# comms_sys_schematic_V1.net
KiCad netlist of a schematic drawn in EAGLE
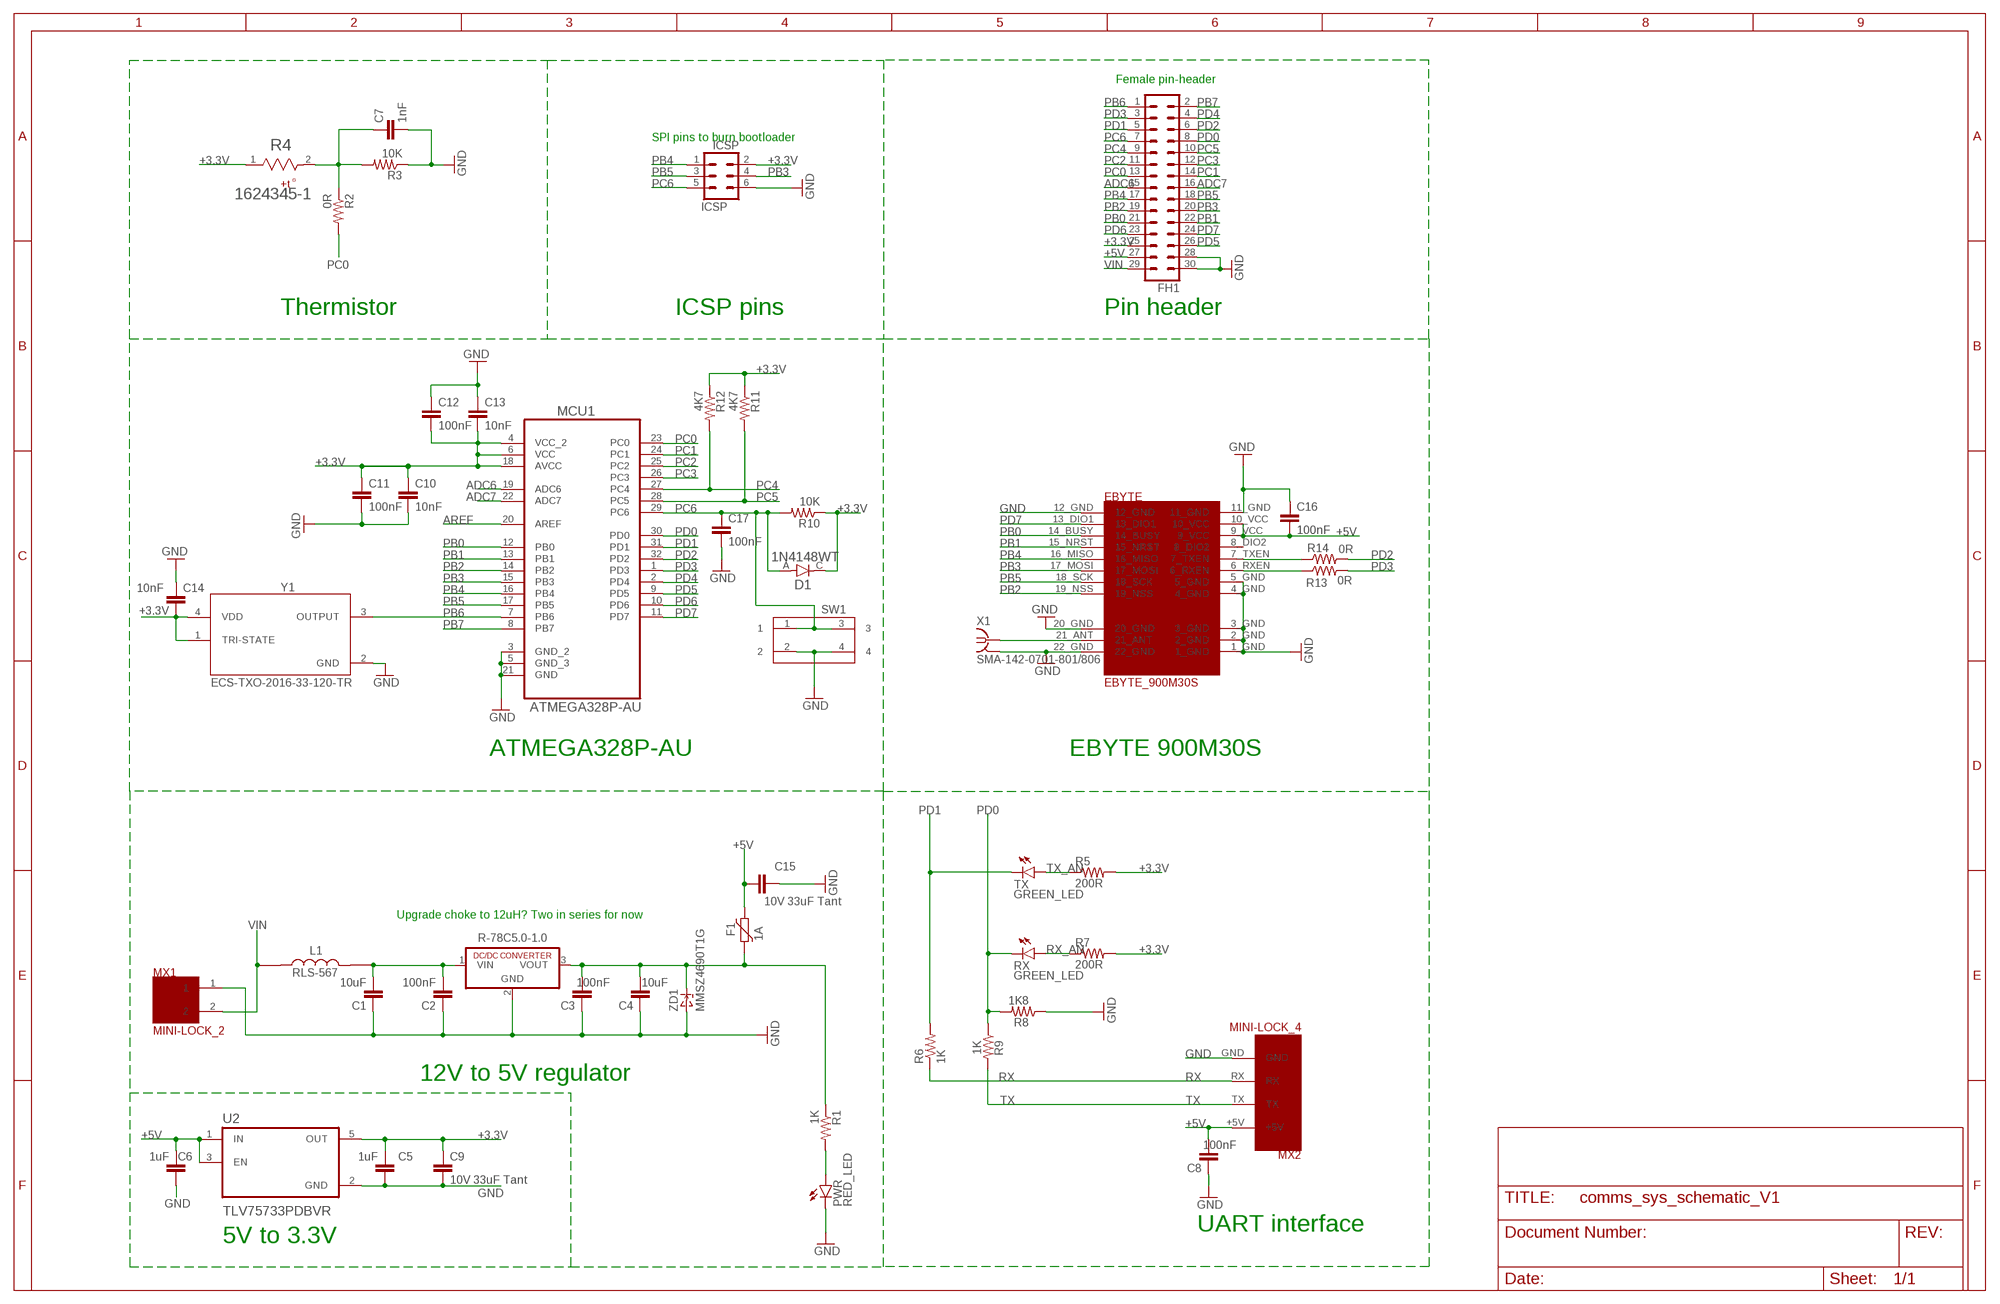
[diagram p0: schematic, sheet 1]

(export (version "E")
  (design (tool "Eeschema 10.0.6"))
  (components
    (comp (ref "C1")
      (value "10uF")
      (footprint "eagle-import:C0805")
      (libsource (lib "eagle-import") (part "C-EUC0805"))
    )
    (comp (ref "C2")
      (value "100nF")
      (footprint "eagle-import:C0805")
      (libsource (lib "eagle-import") (part "C-EUC0805"))
    )
    (comp (ref "C3")
      (value "100nF")
      (footprint "eagle-import:C0805")
      (libsource (lib "eagle-import") (part "C-EUC0805"))
    )
    (comp (ref "C4")
      (value "10uF")
      (footprint "eagle-import:C0805")
      (libsource (lib "eagle-import") (part "C-EUC0805"))
    )
    (comp (ref "C5")
      (value "1uF")
      (footprint "eagle-import:C0805")
      (libsource (lib "eagle-import") (part "C-EUC0805"))
    )
    (comp (ref "C6")
      (value "1uF")
      (footprint "eagle-import:C0805")
      (libsource (lib "eagle-import") (part "C-EUC0805"))
    )
    (comp (ref "C7")
      (value "1nF")
      (footprint "eagle-import:C0805")
      (libsource (lib "eagle-import") (part "C-EUC0805"))
    )
    (comp (ref "C8")
      (value "100nF")
      (footprint "eagle-import:C0805")
      (libsource (lib "eagle-import") (part "C-EUC0805"))
    )
    (comp (ref "C9")
      (value "10V 33uF Tant")
      (footprint "eagle-import:C1206")
      (libsource (lib "eagle-import") (part "C-EUC1206"))
    )
    (comp (ref "C10")
      (value "10nF")
      (footprint "eagle-import:C0805")
      (libsource (lib "eagle-import") (part "C-EUC0805"))
    )
    (comp (ref "C11")
      (value "100nF")
      (footprint "eagle-import:C0805")
      (libsource (lib "eagle-import") (part "C-EUC0805"))
    )
    (comp (ref "C12")
      (value "100nF")
      (footprint "eagle-import:C0805")
      (libsource (lib "eagle-import") (part "C-EUC0805"))
    )
    (comp (ref "C13")
      (value "10nF")
      (footprint "eagle-import:C0805")
      (libsource (lib "eagle-import") (part "C-EUC0805"))
    )
    (comp (ref "C14")
      (value "10nF")
      (footprint "eagle-import:C0805")
      (libsource (lib "eagle-import") (part "C-EUC0805"))
    )
    (comp (ref "C15")
      (value "10V 33uF Tant")
      (footprint "eagle-import:C1206")
      (libsource (lib "eagle-import") (part "C-EUC1206"))
    )
    (comp (ref "C16")
      (value "100nF")
      (footprint "eagle-import:C0805")
      (libsource (lib "eagle-import") (part "C-EUC0805"))
    )
    (comp (ref "C17")
      (value "100nF")
      (footprint "eagle-import:C0805")
      (libsource (lib "eagle-import") (part "C-EUC0805"))
    )
    (comp (ref "D1")
      (value "1N4148WT")
      (footprint "eagle-import:SODFL1608X70N")
      (fields (field (name "DIGI-KEY_PART_NUMBER") "1N4148WTCT-ND") (field (name "MF") "ON Semiconductor"))
      (libsource (lib "eagle-import") (part "1N4148WT"))
    )
    (comp (ref "EBYTE")
      (value "EBYTE_900M30S")
      (footprint "eagle-import:EBYTE_SX1262_900M30S_FOOTPRINT")
      (libsource (lib "eagle-import") (part "EBYTE_SX1262_900M30S"))
    )
    (comp (ref "F1")
      (value "1A")
      (footprint "eagle-import:PTC0805")
      (libsource (lib "eagle-import") (part "FUSE_PTC-0805"))
    )
    (comp (ref "FH1")
      (value "MA15-2")
      (footprint "eagle-import:MA15-2")
      (libsource (lib "eagle-import") (part "MA15-2"))
    )
    (comp (ref "ICSP")
      (value "ICSP")
      (footprint "eagle-import:MA03-2")
      (libsource (lib "eagle-import") (part "MA03-2"))
    )
    (comp (ref "L1")
      (value "RLS-567")
      (footprint "eagle-import:IND_RLS-567")
      (fields (field (name "MF") "Recom Power"))
      (libsource (lib "eagle-import") (part "RLS-567"))
    )
    (comp (ref "MCU1")
      (value "ATMEGA328P-AU")
      (footprint "eagle-import:QFP80P900X900X120-32N")
      (libsource (lib "eagle-import") (part "ATMEGA328P-AU"))
    )
    (comp (ref "MX1")
      (value "MINI-LOCK_2")
      (footprint "eagle-import:MINI-LOCK_2")
      (libsource (lib "eagle-import") (part "MINI-LOCK_2"))
    )
    (comp (ref "MX2")
      (value "MINI-LOCK_4")
      (footprint "eagle-import:MINI-LOCK_4")
      (libsource (lib "eagle-import") (part "MINI-LOCK_4"))
    )
    (comp (ref "PWR")
      (value "RED_LED")
      (footprint "eagle-import:CHIP-LED0805")
      (libsource (lib "eagle-import") (part "LEDCHIP-LED0805"))
    )
    (comp (ref "R1")
      (value "1K")
      (footprint "eagle-import:R0805")
      (libsource (lib "eagle-import") (part "R-US_R0805"))
    )
    (comp (ref "R2")
      (value "0R")
      (footprint "eagle-import:R0805")
      (libsource (lib "eagle-import") (part "R-US_R0805"))
    )
    (comp (ref "R3")
      (value "10K")
      (footprint "eagle-import:R0805")
      (libsource (lib "eagle-import") (part "R-US_R0805"))
    )
    (comp (ref "R4")
      (value "1624345-1")
      (footprint "eagle-import:THRMC2012X50N")
      (fields
        (field (name "DIGI-KEY_PART_NUMBER") "A106104CT-ND")
        (field (name "MF") "TE Connectivity")
        (field (name "MP") "NTC0805J10K")
      )
      (libsource (lib "eagle-import") (part "1624345-1"))
    )
    (comp (ref "R5")
      (value "200R")
      (footprint "eagle-import:R0805")
      (libsource (lib "eagle-import") (part "R-US_R0805"))
    )
    (comp (ref "R6")
      (value "1K")
      (footprint "eagle-import:R0805")
      (libsource (lib "eagle-import") (part "R-US_R0805"))
    )
    (comp (ref "R7")
      (value "200R")
      (footprint "eagle-import:R0805")
      (libsource (lib "eagle-import") (part "R-US_R0805"))
    )
    (comp (ref "R8")
      (value "1K8")
      (footprint "eagle-import:R0805")
      (libsource (lib "eagle-import") (part "R-US_R0805"))
    )
    (comp (ref "R9")
      (value "1K")
      (footprint "eagle-import:R0805")
      (libsource (lib "eagle-import") (part "R-US_R0805"))
    )
    (comp (ref "R10")
      (value "10K")
      (footprint "eagle-import:R0805")
      (libsource (lib "eagle-import") (part "R-US_R0805"))
    )
    (comp (ref "R11")
      (value "4K7")
      (footprint "eagle-import:R0805")
      (libsource (lib "eagle-import") (part "R-US_R0805"))
    )
    (comp (ref "R12")
      (value "4K7")
      (footprint "eagle-import:R0805")
      (libsource (lib "eagle-import") (part "R-US_R0805"))
    )
    (comp (ref "R13")
      (value "0R")
      (footprint "eagle-import:R0805")
      (libsource (lib "eagle-import") (part "R-US_R0805"))
    )
    (comp (ref "R14")
      (value "0R")
      (footprint "eagle-import:R0805")
      (libsource (lib "eagle-import") (part "R-US_R0805"))
    )
    (comp (ref "RX")
      (value "GREEN_LED")
      (footprint "eagle-import:CHIP-LED0805")
      (libsource (lib "eagle-import") (part "LEDCHIP-LED0805"))
    )
    (comp (ref "SW1")
      (value "430152043826")
      (footprint "eagle-import:430152043826")
      (libsource (lib "eagle-import") (part "430152043826"))
    )
    (comp (ref "TX")
      (value "GREEN_LED")
      (footprint "eagle-import:CHIP-LED0805")
      (libsource (lib "eagle-import") (part "LEDCHIP-LED0805"))
    )
    (comp (ref "U1")
      (value "R-78C5.0-1.0")
      (footprint "eagle-import:SIP3")
      (libsource (lib "eagle-import") (part "R-78C-1.05.0"))
    )
    (comp (ref "U2")
      (value "TLV75733PDBVR")
      (footprint "eagle-import:SOT95P280X145-5N")
      (fields (field (name "DIGI-KEY_PART_NUMBER") "296-50414-1-ND") (field (name "MF") "Texas Instruments"))
      (libsource (lib "eagle-import") (part "TLV75733PDBVR"))
    )
    (comp (ref "X1")
      (value "SMA-142-0701-801/806")
      (footprint "eagle-import:J502-ND-142-0701-801_806")
      (fields (field (name "MF") "JOHNSON COMPONENTS") (field (name "MPN") "142-0701-801"))
      (libsource (lib "eagle-import") (part "SMA-142-0701-801/806"))
    )
    (comp (ref "Y1")
      (value "ECS-TXO-2016-33-120-TR")
      (footprint "eagle-import:OSC_ECS-TXO-2016-33-120-TR")
      (fields (field (name "DIGI-KEY_PART_NUMBER") "XC3160CT-ND") (field (name "MF") "ECS Inc."))
      (libsource (lib "eagle-import") (part "ECS-TXO-2016-33-120-TR"))
    )
    (comp (ref "ZD1")
      (value "MMSZ4690T1G")
      (footprint "eagle-import:SOD-123")
      (libsource (lib "eagle-import") (part "ZENERSOD-123"))
    )
  )
  (nets
    (net (code "1") (name "/+3.3V") (class "Default")
      (node (ref "C10") (pin "1") (pinfunction "1_1") (pintype "passive"))
      (node (ref "C11") (pin "1") (pinfunction "1_1") (pintype "passive"))
      (node (ref "C12") (pin "2") (pinfunction "2_2") (pintype "passive"))
      (node (ref "C13") (pin "2") (pinfunction "2_2") (pintype "passive"))
      (node (ref "C14") (pin "2") (pinfunction "2_2") (pintype "passive"))
      (node (ref "C5") (pin "2") (pinfunction "2_2") (pintype "passive"))
      (node (ref "C9") (pin "1") (pinfunction "1_1") (pintype "passive"))
      (node (ref "D1") (pin "C") (pinfunction "C_C") (pintype "passive"))
      (node (ref "FH1") (pin "25") (pinfunction "29_25") (pintype "passive"))
      (node (ref "ICSP") (pin "2") (pinfunction "2_2") (pintype "passive"))
      (node (ref "MCU1") (pin "18") (pinfunction "AVCC_18") (pintype "power_in"))
      (node (ref "MCU1") (pin "4") (pinfunction "VCC_2_4") (pintype "power_in"))
      (node (ref "MCU1") (pin "6") (pinfunction "VCC_6") (pintype "power_in"))
      (node (ref "R10") (pin "1") (pinfunction "1_1") (pintype "passive"))
      (node (ref "R11") (pin "1") (pinfunction "1_1") (pintype "passive"))
      (node (ref "R12") (pin "1") (pinfunction "1_1") (pintype "passive"))
      (node (ref "R4") (pin "1") (pinfunction "1_1") (pintype "passive"))
      (node (ref "R5") (pin "2") (pinfunction "2_2") (pintype "passive"))
      (node (ref "R7") (pin "2") (pinfunction "2_2") (pintype "passive"))
      (node (ref "U2") (pin "5") (pinfunction "OUT_5") (pintype "output"))
      (node (ref "Y1") (pin "1") (pinfunction "TRI-STATE_1") (pintype "input"))
      (node (ref "Y1") (pin "4") (pinfunction "VDD_4") (pintype "input"))
    )
    (net (code "2") (name "/+5V") (class "Default")
      (node (ref "C15") (pin "1") (pinfunction "1_1") (pintype "passive"))
      (node (ref "C16") (pin "2") (pinfunction "2_2") (pintype "passive"))
      (node (ref "C6") (pin "2") (pinfunction "2_2") (pintype "passive"))
      (node (ref "C8") (pin "2") (pinfunction "2_2") (pintype "passive"))
      (node (ref "EBYTE") (pin "10_VCC") (pinfunction "10_VCC_10_VCC") (pintype "power_in"))
      (node (ref "EBYTE") (pin "9_VCC") (pinfunction "9_VCC_9_VCC") (pintype "power_in"))
      (node (ref "F1") (pin "2") (pinfunction "2_2") (pintype "passive"))
      (node (ref "FH1") (pin "27") (pinfunction "31_27") (pintype "passive"))
      (node (ref "MX2") (pin "+5V") (pinfunction "+5V_+5V") (pintype "bidirectional"))
      (node (ref "U2") (pin "1") (pinfunction "IN_1") (pintype "input"))
      (node (ref "U2") (pin "3") (pinfunction "EN_3") (pintype "bidirectional"))
    )
    (net (code "3") (name "/ADC6") (class "Default")
      (node (ref "FH1") (pin "15") (pinfunction "19_15") (pintype "passive"))
      (node (ref "MCU1") (pin "19") (pinfunction "ADC6_19") (pintype "input"))
    )
    (net (code "4") (name "/ADC7") (class "Default")
      (node (ref "FH1") (pin "16") (pinfunction "20_16") (pintype "passive"))
      (node (ref "MCU1") (pin "22") (pinfunction "ADC7_22") (pintype "input"))
    )
    (net (code "5") (name "/AREF") (class "Default")
      (node (ref "MCU1") (pin "20") (pinfunction "AREF_20") (pintype "input"))
    )
    (net (code "6") (name "/PB0") (class "Default")
      (node (ref "EBYTE") (pin "14_BUSY") (pinfunction "14_BUSY_14_BUSY") (pintype "bidirectional"))
      (node (ref "FH1") (pin "21") (pinfunction "25_21") (pintype "passive"))
      (node (ref "MCU1") (pin "12") (pinfunction "PB0_12") (pintype "bidirectional"))
    )
    (net (code "7") (name "/PB1") (class "Default")
      (node (ref "EBYTE") (pin "15_NRST") (pinfunction "15_NRST_15_NRST") (pintype "bidirectional"))
      (node (ref "FH1") (pin "22") (pinfunction "26_22") (pintype "passive"))
      (node (ref "MCU1") (pin "13") (pinfunction "PB1_13") (pintype "bidirectional"))
    )
    (net (code "8") (name "/PB2") (class "Default")
      (node (ref "EBYTE") (pin "19_NSS") (pinfunction "19_NSS_19_NSS") (pintype "bidirectional"))
      (node (ref "FH1") (pin "19") (pinfunction "23_19") (pintype "passive"))
      (node (ref "MCU1") (pin "14") (pinfunction "PB2_14") (pintype "bidirectional"))
    )
    (net (code "9") (name "/PB3") (class "Default")
      (node (ref "EBYTE") (pin "17_MOSI") (pinfunction "17_MOSI_17_MOSI") (pintype "bidirectional"))
      (node (ref "FH1") (pin "20") (pinfunction "24_20") (pintype "passive"))
      (node (ref "ICSP") (pin "4") (pinfunction "4_4") (pintype "passive"))
      (node (ref "MCU1") (pin "15") (pinfunction "PB3_15") (pintype "bidirectional"))
    )
    (net (code "10") (name "/PB4") (class "Default")
      (node (ref "EBYTE") (pin "16_MISO") (pinfunction "16_MISO_16_MISO") (pintype "bidirectional"))
      (node (ref "FH1") (pin "17") (pinfunction "21_17") (pintype "passive"))
      (node (ref "ICSP") (pin "1") (pinfunction "1_1") (pintype "passive"))
      (node (ref "MCU1") (pin "16") (pinfunction "PB4_16") (pintype "bidirectional"))
    )
    (net (code "11") (name "/PB5") (class "Default")
      (node (ref "EBYTE") (pin "18_SCK") (pinfunction "18_SCK_18_SCK") (pintype "bidirectional"))
      (node (ref "FH1") (pin "18") (pinfunction "22_18") (pintype "passive"))
      (node (ref "ICSP") (pin "3") (pinfunction "3_3") (pintype "passive"))
      (node (ref "MCU1") (pin "17") (pinfunction "PB5_17") (pintype "bidirectional"))
    )
    (net (code "12") (name "/PB6") (class "Default")
      (node (ref "FH1") (pin "1") (pinfunction "5_1") (pintype "passive"))
      (node (ref "MCU1") (pin "7") (pinfunction "PB6_7") (pintype "bidirectional"))
      (node (ref "Y1") (pin "3") (pinfunction "OUTPUT_3") (pintype "output"))
    )
    (net (code "13") (name "/PB7") (class "Default")
      (node (ref "FH1") (pin "2") (pinfunction "6_2") (pintype "passive"))
      (node (ref "MCU1") (pin "8") (pinfunction "PB7_8") (pintype "bidirectional"))
    )
    (net (code "14") (name "/PC0") (class "Default")
      (node (ref "FH1") (pin "13") (pinfunction "17_13") (pintype "passive"))
      (node (ref "MCU1") (pin "23") (pinfunction "PC0_23") (pintype "bidirectional"))
      (node (ref "R2") (pin "2") (pinfunction "2_2") (pintype "passive"))
    )
    (net (code "15") (name "/PC1") (class "Default")
      (node (ref "FH1") (pin "14") (pinfunction "18_14") (pintype "passive"))
      (node (ref "MCU1") (pin "24") (pinfunction "PC1_24") (pintype "bidirectional"))
    )
    (net (code "16") (name "/PC2") (class "Default")
      (node (ref "FH1") (pin "11") (pinfunction "15_11") (pintype "passive"))
      (node (ref "MCU1") (pin "25") (pinfunction "PC2_25") (pintype "bidirectional"))
    )
    (net (code "17") (name "/PC3") (class "Default")
      (node (ref "FH1") (pin "12") (pinfunction "16_12") (pintype "passive"))
      (node (ref "MCU1") (pin "26") (pinfunction "PC3_26") (pintype "bidirectional"))
    )
    (net (code "18") (name "/PC4") (class "Default")
      (node (ref "FH1") (pin "9") (pinfunction "13_9") (pintype "passive"))
      (node (ref "MCU1") (pin "27") (pinfunction "PC4_27") (pintype "bidirectional"))
      (node (ref "R12") (pin "2") (pinfunction "2_2") (pintype "passive"))
    )
    (net (code "19") (name "/PC5") (class "Default")
      (node (ref "FH1") (pin "10") (pinfunction "14_10") (pintype "passive"))
      (node (ref "MCU1") (pin "28") (pinfunction "PC5_28") (pintype "bidirectional"))
      (node (ref "R11") (pin "2") (pinfunction "2_2") (pintype "passive"))
    )
    (net (code "20") (name "/PC6") (class "Default")
      (node (ref "C17") (pin "1") (pinfunction "1_1") (pintype "passive"))
      (node (ref "D1") (pin "A") (pinfunction "A_A") (pintype "passive"))
      (node (ref "FH1") (pin "7") (pinfunction "11_7") (pintype "passive"))
      (node (ref "ICSP") (pin "5") (pinfunction "5_5") (pintype "passive"))
      (node (ref "MCU1") (pin "29") (pinfunction "PC6_29") (pintype "bidirectional"))
      (node (ref "R10") (pin "2") (pinfunction "2_2") (pintype "passive"))
      (node (ref "SW1") (pin "1") (pinfunction "1_1") (pintype "bidirectional"))
      (node (ref "SW1") (pin "3") (pinfunction "3_3") (pintype "bidirectional"))
    )
    (net (code "21") (name "/PD0") (class "Default")
      (node (ref "FH1") (pin "8") (pinfunction "12_8") (pintype "passive"))
      (node (ref "MCU1") (pin "30") (pinfunction "PD0_30") (pintype "bidirectional"))
      (node (ref "R8") (pin "2") (pinfunction "2_2") (pintype "passive"))
      (node (ref "R9") (pin "1") (pinfunction "1_1") (pintype "passive"))
      (node (ref "RX") (pin "C") (pinfunction "C_C") (pintype "passive"))
    )
    (net (code "22") (name "/PD1") (class "Default")
      (node (ref "FH1") (pin "5") (pinfunction "9_5") (pintype "passive"))
      (node (ref "MCU1") (pin "31") (pinfunction "PD1_31") (pintype "bidirectional"))
      (node (ref "R6") (pin "2") (pinfunction "2_2") (pintype "passive"))
      (node (ref "TX") (pin "C") (pinfunction "C_C") (pintype "passive"))
    )
    (net (code "23") (name "/PD2") (class "Default")
      (node (ref "FH1") (pin "6") (pinfunction "10_6") (pintype "passive"))
      (node (ref "MCU1") (pin "32") (pinfunction "PD2_32") (pintype "bidirectional"))
      (node (ref "R14") (pin "2") (pinfunction "2_2") (pintype "passive"))
    )
    (net (code "24") (name "/PD3") (class "Default")
      (node (ref "FH1") (pin "3") (pinfunction "7_3") (pintype "passive"))
      (node (ref "MCU1") (pin "1") (pinfunction "PD3_1") (pintype "bidirectional"))
      (node (ref "R13") (pin "2") (pinfunction "2_2") (pintype "passive"))
    )
    (net (code "25") (name "/PD4") (class "Default")
      (node (ref "FH1") (pin "4") (pinfunction "8_4") (pintype "passive"))
      (node (ref "MCU1") (pin "2") (pinfunction "PD4_2") (pintype "bidirectional"))
    )
    (net (code "26") (name "/PD5") (class "Default")
      (node (ref "FH1") (pin "26") (pinfunction "30_26") (pintype "passive"))
      (node (ref "MCU1") (pin "9") (pinfunction "PD5_9") (pintype "bidirectional"))
    )
    (net (code "27") (name "/PD6") (class "Default")
      (node (ref "FH1") (pin "23") (pinfunction "27_23") (pintype "passive"))
      (node (ref "MCU1") (pin "10") (pinfunction "PD6_10") (pintype "bidirectional"))
    )
    (net (code "28") (name "/PD7") (class "Default")
      (node (ref "EBYTE") (pin "13_DIO1") (pinfunction "13_DIO1_13_DIO1") (pintype "bidirectional"))
      (node (ref "FH1") (pin "24") (pinfunction "28_24") (pintype "passive"))
      (node (ref "MCU1") (pin "11") (pinfunction "PD7_11") (pintype "bidirectional"))
    )
    (net (code "29") (name "/RX") (class "Default")
      (node (ref "MX2") (pin "RX") (pinfunction "RX_RX") (pintype "bidirectional"))
      (node (ref "R6") (pin "1") (pinfunction "1_1") (pintype "passive"))
    )
    (net (code "30") (name "/RX_AN") (class "Default")
      (node (ref "R7") (pin "1") (pinfunction "1_1") (pintype "passive"))
      (node (ref "RX") (pin "A") (pinfunction "A_A") (pintype "passive"))
    )
    (net (code "31") (name "/TX") (class "Default")
      (node (ref "MX2") (pin "TX") (pinfunction "TX_TX") (pintype "bidirectional"))
      (node (ref "R9") (pin "2") (pinfunction "2_2") (pintype "passive"))
    )
    (net (code "32") (name "/TX_AN") (class "Default")
      (node (ref "R5") (pin "1") (pinfunction "1_1") (pintype "passive"))
      (node (ref "TX") (pin "A") (pinfunction "A_A") (pintype "passive"))
    )
    (net (code "33") (name "/VIN") (class "Default")
      (node (ref "FH1") (pin "29") (pinfunction "33_29") (pintype "passive"))
      (node (ref "L1") (pin "1") (pinfunction "1_1") (pintype "passive"))
      (node (ref "MX1") (pin "2") (pinfunction "2_2") (pintype "bidirectional"))
    )
    (net (code "34") (name "GND") (class "Default")
      (node (ref "C1") (pin "1") (pinfunction "1_1") (pintype "passive"))
      (node (ref "C10") (pin "2") (pinfunction "2_2") (pintype "passive"))
      (node (ref "C11") (pin "2") (pinfunction "2_2") (pintype "passive"))
      (node (ref "C12") (pin "1") (pinfunction "1_1") (pintype "passive"))
      (node (ref "C13") (pin "1") (pinfunction "1_1") (pintype "passive"))
      (node (ref "C14") (pin "1") (pinfunction "1_1") (pintype "passive"))
      (node (ref "C15") (pin "2") (pinfunction "2_2") (pintype "passive"))
      (node (ref "C16") (pin "1") (pinfunction "1_1") (pintype "passive"))
      (node (ref "C17") (pin "2") (pinfunction "2_2") (pintype "passive"))
      (node (ref "C2") (pin "1") (pinfunction "1_1") (pintype "passive"))
      (node (ref "C3") (pin "1") (pinfunction "1_1") (pintype "passive"))
      (node (ref "C4") (pin "1") (pinfunction "1_1") (pintype "passive"))
      (node (ref "C5") (pin "1") (pinfunction "1_1") (pintype "passive"))
      (node (ref "C6") (pin "1") (pinfunction "1_1") (pintype "passive"))
      (node (ref "C7") (pin "2") (pinfunction "2_2") (pintype "passive"))
      (node (ref "C8") (pin "1") (pinfunction "1_1") (pintype "passive"))
      (node (ref "C9") (pin "2") (pinfunction "2_2") (pintype "passive"))
      (node (ref "EBYTE") (pin "11_GND") (pinfunction "11_GND_11_GND") (pintype "power_in"))
      (node (ref "EBYTE") (pin "12_GND") (pinfunction "12_GND_12_GND") (pintype "power_in"))
      (node (ref "EBYTE") (pin "1_GND") (pinfunction "1_GND_1_GND") (pintype "power_in"))
      (node (ref "EBYTE") (pin "20_GND") (pinfunction "20_GND_20_GND") (pintype "power_in"))
      (node (ref "EBYTE") (pin "22_GND") (pinfunction "22_GND_22_GND") (pintype "power_in"))
      (node (ref "EBYTE") (pin "2_GND") (pinfunction "2_GND_2_GND") (pintype "power_in"))
      (node (ref "EBYTE") (pin "3_GND") (pinfunction "3_GND_3_GND") (pintype "power_in"))
      (node (ref "EBYTE") (pin "4_GND") (pinfunction "4_GND_4_GND") (pintype "power_in"))
      (node (ref "EBYTE") (pin "5_GND") (pinfunction "5_GND_5_GND") (pintype "power_in"))
      (node (ref "FH1") (pin "28") (pinfunction "32_28") (pintype "passive"))
      (node (ref "FH1") (pin "30") (pinfunction "34_30") (pintype "passive"))
      (node (ref "ICSP") (pin "6") (pinfunction "6_6") (pintype "passive"))
      (node (ref "MCU1") (pin "21") (pinfunction "GND_21") (pintype "passive"))
      (node (ref "MCU1") (pin "3") (pinfunction "GND_2_3") (pintype "passive"))
      (node (ref "MCU1") (pin "5") (pinfunction "GND_3_5") (pintype "passive"))
      (node (ref "MX1") (pin "1") (pinfunction "1_1") (pintype "bidirectional"))
      (node (ref "MX2") (pin "GND") (pinfunction "GND_GND") (pintype "bidirectional"))
      (node (ref "PWR") (pin "C") (pinfunction "C_C") (pintype "passive"))
      (node (ref "R3") (pin "1") (pinfunction "1_1") (pintype "passive"))
      (node (ref "R8") (pin "1") (pinfunction "1_1") (pintype "passive"))
      (node (ref "SW1") (pin "2") (pinfunction "2_2") (pintype "bidirectional"))
      (node (ref "SW1") (pin "4") (pinfunction "4_4") (pintype "bidirectional"))
      (node (ref "U1") (pin "2") (pinfunction "GND_2") (pintype "passive"))
      (node (ref "U2") (pin "2") (pinfunction "GND_2") (pintype "power_in"))
      (node (ref "X1") (pin "G@1") (pinfunction "2_G@1") (pintype "passive"))
      (node (ref "X1") (pin "G@2") (pinfunction "2_G@2") (pintype "passive"))
      (node (ref "X1") (pin "G@3") (pinfunction "2_G@3") (pintype "passive"))
      (node (ref "X1") (pin "G@4") (pinfunction "2_G@4") (pintype "passive"))
      (node (ref "Y1") (pin "2") (pinfunction "GND_2") (pintype "power_in"))
      (node (ref "ZD1") (pin "A") (pinfunction "A_A") (pintype "passive"))
    )
    (net (code "35") (name "Net-(C7-Pad1)") (class "Default")
      (node (ref "C7") (pin "1") (pinfunction "1_1") (pintype "passive"))
      (node (ref "R2") (pin "1") (pinfunction "1_1") (pintype "passive"))
      (node (ref "R3") (pin "2") (pinfunction "2_2") (pintype "passive"))
      (node (ref "R4") (pin "2") (pinfunction "2_2") (pintype "passive"))
    )
    (net (code "36") (name "Net-(EBYTE-Pad6_RXEN)") (class "Default")
      (node (ref "EBYTE") (pin "6_RXEN") (pinfunction "6_RXEN_6_RXEN") (pintype "bidirectional"))
      (node (ref "R13") (pin "1") (pinfunction "1_1") (pintype "passive"))
    )
    (net (code "37") (name "Net-(EBYTE-Pad7_TXEN)") (class "Default")
      (node (ref "EBYTE") (pin "7_TXEN") (pinfunction "7_TXEN_7_TXEN") (pintype "bidirectional"))
      (node (ref "R14") (pin "1") (pinfunction "1_1") (pintype "passive"))
    )
    (net (code "38") (name "Net-(EBYTE-Pad21_ANT)") (class "Default")
      (node (ref "EBYTE") (pin "21_ANT") (pinfunction "21_ANT_21_ANT") (pintype "bidirectional"))
      (node (ref "X1") (pin "1") (pinfunction "1_1") (pintype "passive"))
    )
    (net (code "39") (name "Net-(PWR-PadA)") (class "Default")
      (node (ref "PWR") (pin "A") (pinfunction "A_A") (pintype "passive"))
      (node (ref "R1") (pin "2") (pinfunction "2_2") (pintype "passive"))
    )
    (net (code "40") (name "Net-(U1-VIN)") (class "Default")
      (node (ref "C1") (pin "2") (pinfunction "2_2") (pintype "passive"))
      (node (ref "C2") (pin "2") (pinfunction "2_2") (pintype "passive"))
      (node (ref "L1") (pin "2") (pinfunction "2_2") (pintype "passive"))
      (node (ref "U1") (pin "1") (pinfunction "VIN_1") (pintype "passive"))
    )
    (net (code "41") (name "Net-(U1-VOUT)") (class "Default")
      (node (ref "C3") (pin "2") (pinfunction "2_2") (pintype "passive"))
      (node (ref "C4") (pin "2") (pinfunction "2_2") (pintype "passive"))
      (node (ref "F1") (pin "1") (pinfunction "1_1") (pintype "passive"))
      (node (ref "R1") (pin "1") (pinfunction "1_1") (pintype "passive"))
      (node (ref "U1") (pin "3") (pinfunction "VOUT_3") (pintype "passive"))
      (node (ref "ZD1") (pin "C") (pinfunction "C_C") (pintype "passive"))
    )
    (net (code "42") (name "unconnected-(EBYTE-Pad8_DIO2)") (class "Default")
      (node (ref "EBYTE") (pin "8_DIO2") (pinfunction "8_DIO2_8_DIO2") (pintype "bidirectional"))
    )
  )
)
